# source_eagle.net
KiCad netlist of a schematic drawn in EAGLE
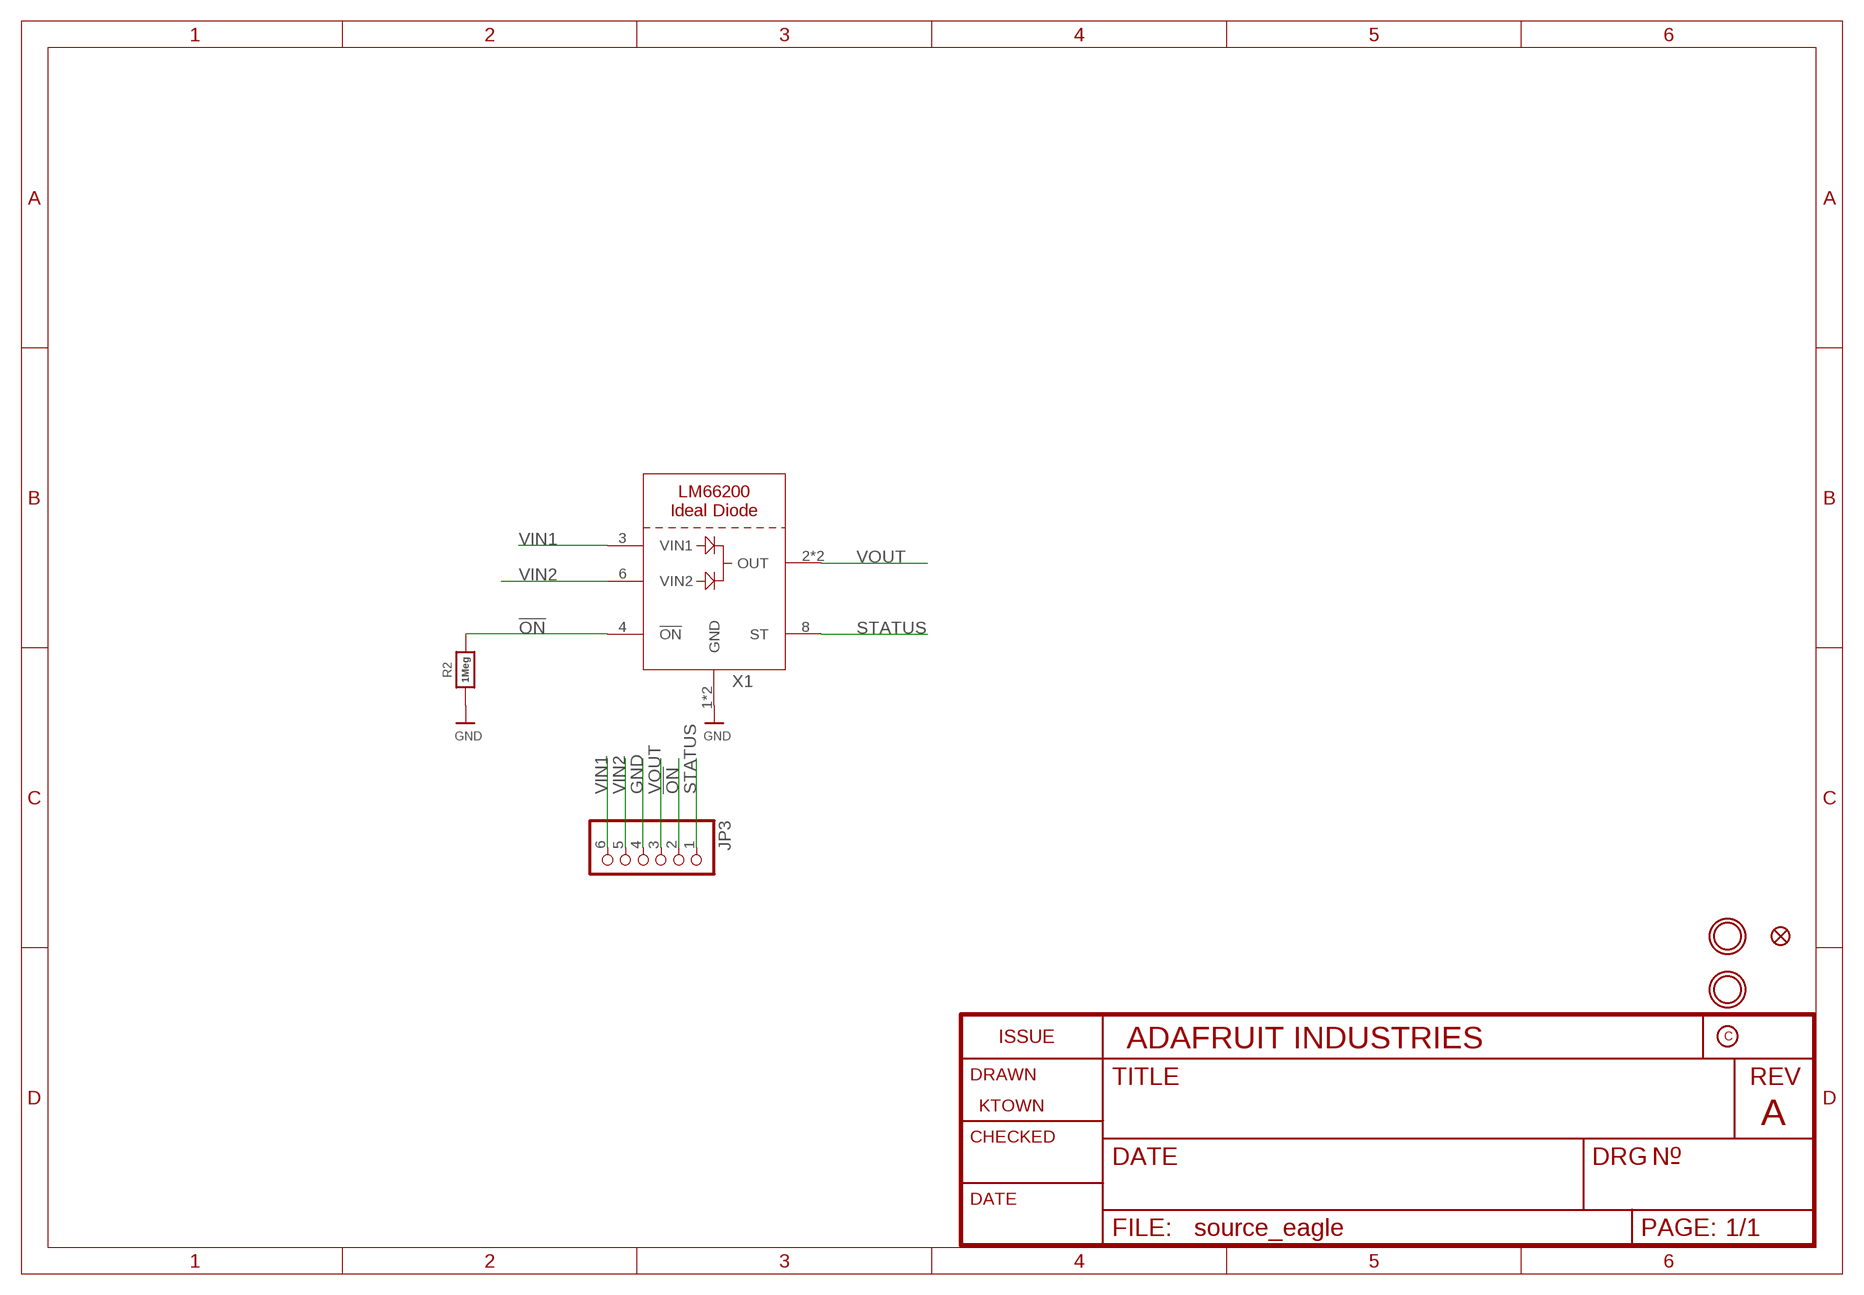
[diagram p0: schematic, sheet 1]

(export (version "E")
  (design (tool "Eeschema 10.0.6"))
  (components
    (comp (ref "FID2")
      (value "FIDUCIAL_1MM")
      (footprint "eagle-import:FIDUCIAL_1MM")
      (libsource (lib "eagle-import") (part "FIDUCIAL_1MM"))
    )
    (comp (ref "JP3")
      (value "HEADER-1X670MIL")
      (footprint "eagle-import:1X06_ROUND_70")
      (libsource (lib "eagle-import") (part "HEADER-1X670MIL"))
    )
    (comp (ref "R2")
      (value "1Meg")
      (footprint "eagle-import:0603-NO")
      (libsource (lib "eagle-import") (part "RESISTOR_0603_NOOUT"))
    )
    (comp (ref "U$1")
      (value "MOUNTINGHOLE2.5")
      (footprint "eagle-import:MOUNTINGHOLE_2.5_PLATED")
      (libsource (lib "eagle-import") (part "MOUNTINGHOLE2.5"))
    )
    (comp (ref "U$9")
      (value "MOUNTINGHOLE2.5")
      (footprint "eagle-import:MOUNTINGHOLE_2.5_PLATED")
      (libsource (lib "eagle-import") (part "MOUNTINGHOLE2.5"))
    )
    (comp (ref "X1")
      (value "LM66200")
      (footprint "eagle-import:SOT583")
      (libsource (lib "eagle-import") (part "LM66200"))
    )
  )
  (nets
    (net (code "1") (name "/STATUS") (class "Default")
      (node (ref "JP3") (pin "1") (pinfunction "1_1") (pintype "passive"))
      (node (ref "X1") (pin "8") (pinfunction "ST_8") (pintype "output"))
    )
    (net (code "2") (name "/VIN1") (class "Default")
      (node (ref "JP3") (pin "6") (pinfunction "6_6") (pintype "passive"))
      (node (ref "X1") (pin "3") (pinfunction "VIN1_3") (pintype "input"))
    )
    (net (code "3") (name "/VIN2") (class "Default")
      (node (ref "JP3") (pin "5") (pinfunction "5_5") (pintype "passive"))
      (node (ref "X1") (pin "6") (pinfunction "VIN2_6") (pintype "input"))
    )
    (net (code "4") (name "/VOUT") (class "Default")
      (node (ref "JP3") (pin "3") (pinfunction "3_3") (pintype "passive"))
      (node (ref "X1") (pin "2") (pinfunction "OUT_2") (pintype "output"))
      (node (ref "X1") (pin "7") (pinfunction "OUT_7") (pintype "output"))
    )
    (net (code "5") (name "/~{ON}") (class "Default")
      (node (ref "JP3") (pin "2") (pinfunction "2_2") (pintype "passive"))
      (node (ref "R2") (pin "2") (pinfunction "2_2") (pintype "passive"))
      (node (ref "X1") (pin "4") (pinfunction "~{ON}_4") (pintype "input"))
    )
    (net (code "6") (name "GND") (class "Default")
      (node (ref "JP3") (pin "4") (pinfunction "4_4") (pintype "passive"))
      (node (ref "R2") (pin "1") (pinfunction "1_1") (pintype "passive"))
      (node (ref "X1") (pin "1") (pinfunction "GND_1") (pintype "power_in"))
      (node (ref "X1") (pin "5") (pinfunction "GND_5") (pintype "power_in"))
    )
  )
)
